# STM32_FYP_Digital_In_Module.net
KiCad netlist of a schematic drawn in Altium Designer
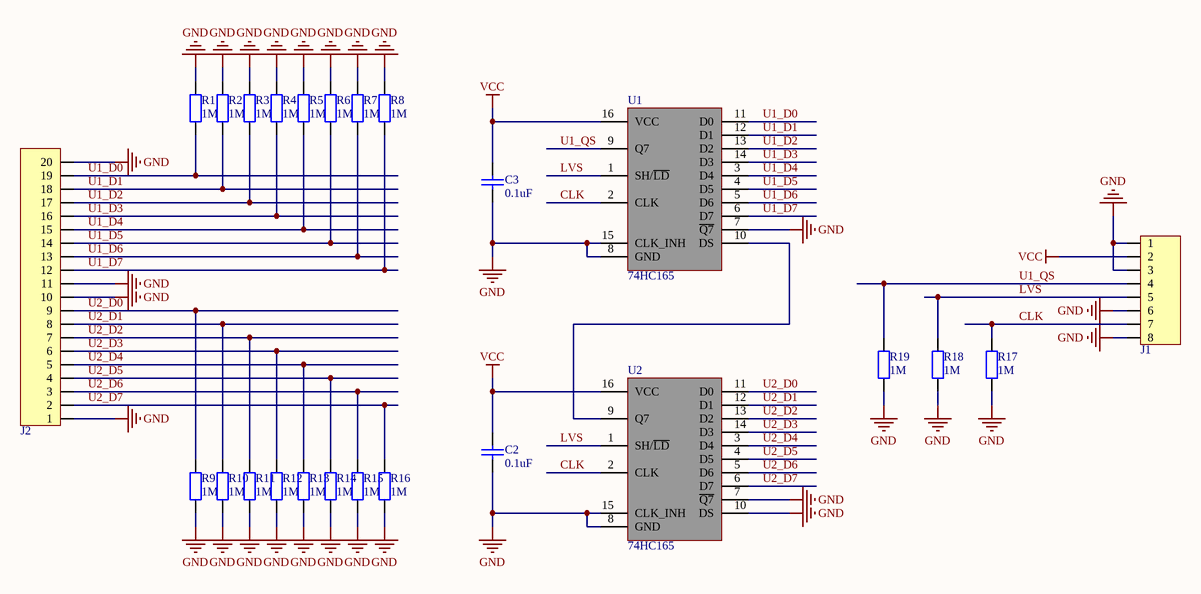
[diagram p0: STM32_FYP_Digital_In_Module.SchDoc]

(export (version "E")
  (design (tool "Eeschema 10.0.6"))
  (components
    (comp (ref "C2")
      (value "0.1uF")
      (footprint "0805C_M")
      (description "无极性电容")
      (fields (field (name "PUBLISHER") "Altium Limited"))
      (libsource (lib "USER") (part "Cap"))
    )
    (comp (ref "C3")
      (value "0.1uF")
      (footprint "0805C_M")
      (description "无极性电容")
      (fields (field (name "PUBLISHER") "Altium Limited"))
      (libsource (lib "USER") (part "Cap"))
    )
    (comp (ref "J1")
      (value "Header8")
      (footprint "user:8P-2.54-H")
      (description "8PIN插座")
      (libsource (lib "USER") (part "Header8"))
    )
    (comp (ref "J2")
      (value "Header20")
      (footprint "USER:20P-2.54-H")
      (description "20PIN插座")
      (libsource (lib "USER") (part "Header20"))
    )
    (comp (ref "R1")
      (value "1M")
      (footprint "0805R_M")
      (description "电阻")
      (fields (field (name "PUBLISHER") "Altium Limited"))
      (libsource (lib "USER") (part "Res"))
    )
    (comp (ref "R2")
      (value "1M")
      (footprint "0805R_M")
      (description "电阻")
      (fields (field (name "PUBLISHER") "Altium Limited"))
      (libsource (lib "USER") (part "Res"))
    )
    (comp (ref "R3")
      (value "1M")
      (footprint "0805R_M")
      (description "电阻")
      (fields (field (name "PUBLISHER") "Altium Limited"))
      (libsource (lib "USER") (part "Res"))
    )
    (comp (ref "R4")
      (value "1M")
      (footprint "0805R_M")
      (description "电阻")
      (fields (field (name "PUBLISHER") "Altium Limited"))
      (libsource (lib "USER") (part "Res"))
    )
    (comp (ref "R5")
      (value "1M")
      (footprint "0805R_M")
      (description "电阻")
      (fields (field (name "PUBLISHER") "Altium Limited"))
      (libsource (lib "USER") (part "Res"))
    )
    (comp (ref "R6")
      (value "1M")
      (footprint "0805R_M")
      (description "电阻")
      (fields (field (name "PUBLISHER") "Altium Limited"))
      (libsource (lib "USER") (part "Res"))
    )
    (comp (ref "R7")
      (value "1M")
      (footprint "0805R_M")
      (description "电阻")
      (fields (field (name "PUBLISHER") "Altium Limited"))
      (libsource (lib "USER") (part "Res"))
    )
    (comp (ref "R8")
      (value "1M")
      (footprint "0805R_M")
      (description "电阻")
      (fields (field (name "PUBLISHER") "Altium Limited"))
      (libsource (lib "USER") (part "Res"))
    )
    (comp (ref "R9")
      (value "1M")
      (footprint "0805R_M")
      (description "电阻")
      (fields (field (name "PUBLISHER") "Altium Limited"))
      (libsource (lib "USER") (part "Res"))
    )
    (comp (ref "R10")
      (value "1M")
      (footprint "0805R_M")
      (description "电阻")
      (fields (field (name "PUBLISHER") "Altium Limited"))
      (libsource (lib "USER") (part "Res"))
    )
    (comp (ref "R11")
      (value "1M")
      (footprint "0805R_M")
      (description "电阻")
      (fields (field (name "PUBLISHER") "Altium Limited"))
      (libsource (lib "USER") (part "Res"))
    )
    (comp (ref "R12")
      (value "1M")
      (footprint "0805R_M")
      (description "电阻")
      (fields (field (name "PUBLISHER") "Altium Limited"))
      (libsource (lib "USER") (part "Res"))
    )
    (comp (ref "R13")
      (value "1M")
      (footprint "0805R_M")
      (description "电阻")
      (fields (field (name "PUBLISHER") "Altium Limited"))
      (libsource (lib "USER") (part "Res"))
    )
    (comp (ref "R14")
      (value "1M")
      (footprint "0805R_M")
      (description "电阻")
      (fields (field (name "PUBLISHER") "Altium Limited"))
      (libsource (lib "USER") (part "Res"))
    )
    (comp (ref "R15")
      (value "1M")
      (footprint "0805R_M")
      (description "电阻")
      (fields (field (name "PUBLISHER") "Altium Limited"))
      (libsource (lib "USER") (part "Res"))
    )
    (comp (ref "R16")
      (value "1M")
      (footprint "0805R_M")
      (description "电阻")
      (fields (field (name "PUBLISHER") "Altium Limited"))
      (libsource (lib "USER") (part "Res"))
    )
    (comp (ref "R17")
      (value "1M")
      (footprint "0805R_M")
      (description "电阻")
      (fields (field (name "PUBLISHER") "Altium Limited"))
      (libsource (lib "USER") (part "Res"))
    )
    (comp (ref "R18")
      (value "1M")
      (footprint "0805R_M")
      (description "电阻")
      (fields (field (name "PUBLISHER") "Altium Limited"))
      (libsource (lib "USER") (part "Res"))
    )
    (comp (ref "R19")
      (value "1M")
      (footprint "0805R_M")
      (description "电阻")
      (fields (field (name "PUBLISHER") "Altium Limited"))
      (libsource (lib "USER") (part "Res"))
    )
    (comp (ref "U1")
      (value "74HC165")
      (footprint "user1:SOIC-16_150mil")
      (description "并入串出移位寄存器")
      (libsource (lib "GUEST") (part "74HC165"))
    )
    (comp (ref "U2")
      (value "74HC165")
      (footprint "user1:SOIC-16_150mil")
      (description "并入串出移位寄存器")
      (libsource (lib "GUEST") (part "74HC165"))
    )
  )
  (nets
    (net (code "1") (name "/CLK") (class "Default")
      (node (ref "J1") (pin "7") (pinfunction "7_7") (pintype "passive"))
      (node (ref "R17") (pin "2") (pinfunction "2_2") (pintype "passive"))
      (node (ref "U1") (pin "2") (pinfunction "CLK_2") (pintype "passive"))
      (node (ref "U2") (pin "2") (pinfunction "CLK_2") (pintype "passive"))
    )
    (net (code "2") (name "/LVS") (class "Default")
      (node (ref "J1") (pin "5") (pinfunction "5_5") (pintype "passive"))
      (node (ref "R18") (pin "2") (pinfunction "2_2") (pintype "passive"))
      (node (ref "U1") (pin "1") (pinfunction "SH/~{LD}_1") (pintype "passive"))
      (node (ref "U2") (pin "1") (pinfunction "SH/~{LD}_1") (pintype "passive"))
    )
    (net (code "3") (name "/U1_D0") (class "Default")
      (node (ref "J2") (pin "19") (pinfunction "19_19") (pintype "passive"))
      (node (ref "R1") (pin "1") (pinfunction "1_1") (pintype "passive"))
      (node (ref "U1") (pin "11") (pinfunction "D0_11") (pintype "passive"))
    )
    (net (code "4") (name "/U1_D1") (class "Default")
      (node (ref "J2") (pin "18") (pinfunction "18_18") (pintype "passive"))
      (node (ref "R2") (pin "1") (pinfunction "1_1") (pintype "passive"))
      (node (ref "U1") (pin "12") (pinfunction "D1_12") (pintype "passive"))
    )
    (net (code "5") (name "/U1_D2") (class "Default")
      (node (ref "J2") (pin "17") (pinfunction "17_17") (pintype "passive"))
      (node (ref "R3") (pin "1") (pinfunction "1_1") (pintype "passive"))
      (node (ref "U1") (pin "13") (pinfunction "D2_13") (pintype "passive"))
    )
    (net (code "6") (name "/U1_D3") (class "Default")
      (node (ref "J2") (pin "16") (pinfunction "16_16") (pintype "passive"))
      (node (ref "R4") (pin "1") (pinfunction "1_1") (pintype "passive"))
      (node (ref "U1") (pin "14") (pinfunction "D3_14") (pintype "passive"))
    )
    (net (code "7") (name "/U1_D4") (class "Default")
      (node (ref "J2") (pin "15") (pinfunction "15_15") (pintype "passive"))
      (node (ref "R5") (pin "1") (pinfunction "1_1") (pintype "passive"))
      (node (ref "U1") (pin "3") (pinfunction "D4_3") (pintype "passive"))
    )
    (net (code "8") (name "/U1_D5") (class "Default")
      (node (ref "J2") (pin "14") (pinfunction "14_14") (pintype "passive"))
      (node (ref "R6") (pin "1") (pinfunction "1_1") (pintype "passive"))
      (node (ref "U1") (pin "4") (pinfunction "D5_4") (pintype "passive"))
    )
    (net (code "9") (name "/U1_D6") (class "Default")
      (node (ref "J2") (pin "13") (pinfunction "13_13") (pintype "passive"))
      (node (ref "R7") (pin "1") (pinfunction "1_1") (pintype "passive"))
      (node (ref "U1") (pin "5") (pinfunction "D6_5") (pintype "passive"))
    )
    (net (code "10") (name "/U1_D7") (class "Default")
      (node (ref "J2") (pin "12") (pinfunction "12_12") (pintype "passive"))
      (node (ref "R8") (pin "1") (pinfunction "1_1") (pintype "passive"))
      (node (ref "U1") (pin "6") (pinfunction "D7_6") (pintype "passive"))
    )
    (net (code "11") (name "/U1_QS") (class "Default")
      (node (ref "J1") (pin "4") (pinfunction "4_4") (pintype "passive"))
      (node (ref "R19") (pin "2") (pinfunction "2_2") (pintype "passive"))
      (node (ref "U1") (pin "9") (pinfunction "Q7_9") (pintype "passive"))
    )
    (net (code "12") (name "/U2_D0") (class "Default")
      (node (ref "J2") (pin "9") (pinfunction "9_9") (pintype "passive"))
      (node (ref "R9") (pin "2") (pinfunction "2_2") (pintype "passive"))
      (node (ref "U2") (pin "11") (pinfunction "D0_11") (pintype "passive"))
    )
    (net (code "13") (name "/U2_D1") (class "Default")
      (node (ref "J2") (pin "8") (pinfunction "8_8") (pintype "passive"))
      (node (ref "R10") (pin "2") (pinfunction "2_2") (pintype "passive"))
      (node (ref "U2") (pin "12") (pinfunction "D1_12") (pintype "passive"))
    )
    (net (code "14") (name "/U2_D2") (class "Default")
      (node (ref "J2") (pin "7") (pinfunction "7_7") (pintype "passive"))
      (node (ref "R11") (pin "2") (pinfunction "2_2") (pintype "passive"))
      (node (ref "U2") (pin "13") (pinfunction "D2_13") (pintype "passive"))
    )
    (net (code "15") (name "/U2_D3") (class "Default")
      (node (ref "J2") (pin "6") (pinfunction "6_6") (pintype "passive"))
      (node (ref "R12") (pin "2") (pinfunction "2_2") (pintype "passive"))
      (node (ref "U2") (pin "14") (pinfunction "D3_14") (pintype "passive"))
    )
    (net (code "16") (name "/U2_D4") (class "Default")
      (node (ref "J2") (pin "5") (pinfunction "5_5") (pintype "passive"))
      (node (ref "R13") (pin "2") (pinfunction "2_2") (pintype "passive"))
      (node (ref "U2") (pin "3") (pinfunction "D4_3") (pintype "passive"))
    )
    (net (code "17") (name "/U2_D5") (class "Default")
      (node (ref "J2") (pin "4") (pinfunction "4_4") (pintype "passive"))
      (node (ref "R14") (pin "2") (pinfunction "2_2") (pintype "passive"))
      (node (ref "U2") (pin "4") (pinfunction "D5_4") (pintype "passive"))
    )
    (net (code "18") (name "/U2_D6") (class "Default")
      (node (ref "J2") (pin "3") (pinfunction "3_3") (pintype "passive"))
      (node (ref "R15") (pin "2") (pinfunction "2_2") (pintype "passive"))
      (node (ref "U2") (pin "5") (pinfunction "D6_5") (pintype "passive"))
    )
    (net (code "19") (name "/U2_D7") (class "Default")
      (node (ref "J2") (pin "2") (pinfunction "2_2") (pintype "passive"))
      (node (ref "R16") (pin "2") (pinfunction "2_2") (pintype "passive"))
      (node (ref "U2") (pin "6") (pinfunction "D7_6") (pintype "passive"))
    )
    (net (code "20") (name "GND") (class "Default")
      (node (ref "C2") (pin "2") (pinfunction "2_2") (pintype "passive"))
      (node (ref "C3") (pin "2") (pinfunction "2_2") (pintype "passive"))
      (node (ref "J1") (pin "1") (pinfunction "1_1") (pintype "passive"))
      (node (ref "J1") (pin "3") (pinfunction "3_3") (pintype "passive"))
      (node (ref "J1") (pin "6") (pinfunction "6_6") (pintype "passive"))
      (node (ref "J1") (pin "8") (pinfunction "8_8") (pintype "passive"))
      (node (ref "J2") (pin "1") (pinfunction "1_1") (pintype "passive"))
      (node (ref "J2") (pin "10") (pinfunction "10_10") (pintype "passive"))
      (node (ref "J2") (pin "11") (pinfunction "11_11") (pintype "passive"))
      (node (ref "J2") (pin "20") (pinfunction "20_20") (pintype "passive"))
      (node (ref "R1") (pin "2") (pinfunction "2_2") (pintype "passive"))
      (node (ref "R10") (pin "1") (pinfunction "1_1") (pintype "passive"))
      (node (ref "R11") (pin "1") (pinfunction "1_1") (pintype "passive"))
      (node (ref "R12") (pin "1") (pinfunction "1_1") (pintype "passive"))
      (node (ref "R13") (pin "1") (pinfunction "1_1") (pintype "passive"))
      (node (ref "R14") (pin "1") (pinfunction "1_1") (pintype "passive"))
      (node (ref "R15") (pin "1") (pinfunction "1_1") (pintype "passive"))
      (node (ref "R16") (pin "1") (pinfunction "1_1") (pintype "passive"))
      (node (ref "R17") (pin "1") (pinfunction "1_1") (pintype "passive"))
      (node (ref "R18") (pin "1") (pinfunction "1_1") (pintype "passive"))
      (node (ref "R19") (pin "1") (pinfunction "1_1") (pintype "passive"))
      (node (ref "R2") (pin "2") (pinfunction "2_2") (pintype "passive"))
      (node (ref "R3") (pin "2") (pinfunction "2_2") (pintype "passive"))
      (node (ref "R4") (pin "2") (pinfunction "2_2") (pintype "passive"))
      (node (ref "R5") (pin "2") (pinfunction "2_2") (pintype "passive"))
      (node (ref "R6") (pin "2") (pinfunction "2_2") (pintype "passive"))
      (node (ref "R7") (pin "2") (pinfunction "2_2") (pintype "passive"))
      (node (ref "R8") (pin "2") (pinfunction "2_2") (pintype "passive"))
      (node (ref "R9") (pin "1") (pinfunction "1_1") (pintype "passive"))
      (node (ref "U1") (pin "15") (pinfunction "CLK_INH_15") (pintype "passive"))
      (node (ref "U1") (pin "7") (pinfunction "~{Q7}_7") (pintype "passive"))
      (node (ref "U1") (pin "8") (pinfunction "GND_8") (pintype "passive"))
      (node (ref "U2") (pin "10") (pinfunction "DS_10") (pintype "passive"))
      (node (ref "U2") (pin "15") (pinfunction "CLK_INH_15") (pintype "passive"))
      (node (ref "U2") (pin "7") (pinfunction "~{Q7}_7") (pintype "passive"))
      (node (ref "U2") (pin "8") (pinfunction "GND_8") (pintype "passive"))
    )
    (net (code "21") (name "Net-(U1-DS)") (class "Default")
      (node (ref "U1") (pin "10") (pinfunction "DS_10") (pintype "passive"))
      (node (ref "U2") (pin "9") (pinfunction "Q7_9") (pintype "passive"))
    )
    (net (code "22") (name "VCC") (class "Default")
      (node (ref "C2") (pin "1") (pinfunction "1_1") (pintype "passive"))
      (node (ref "C3") (pin "1") (pinfunction "1_1") (pintype "passive"))
      (node (ref "J1") (pin "2") (pinfunction "2_2") (pintype "passive"))
      (node (ref "U1") (pin "16") (pinfunction "VCC_16") (pintype "passive"))
      (node (ref "U2") (pin "16") (pinfunction "VCC_16") (pintype "passive"))
    )
  )
)
